# M405X.net
KiCad netlist of a schematic drawn in EAGLE
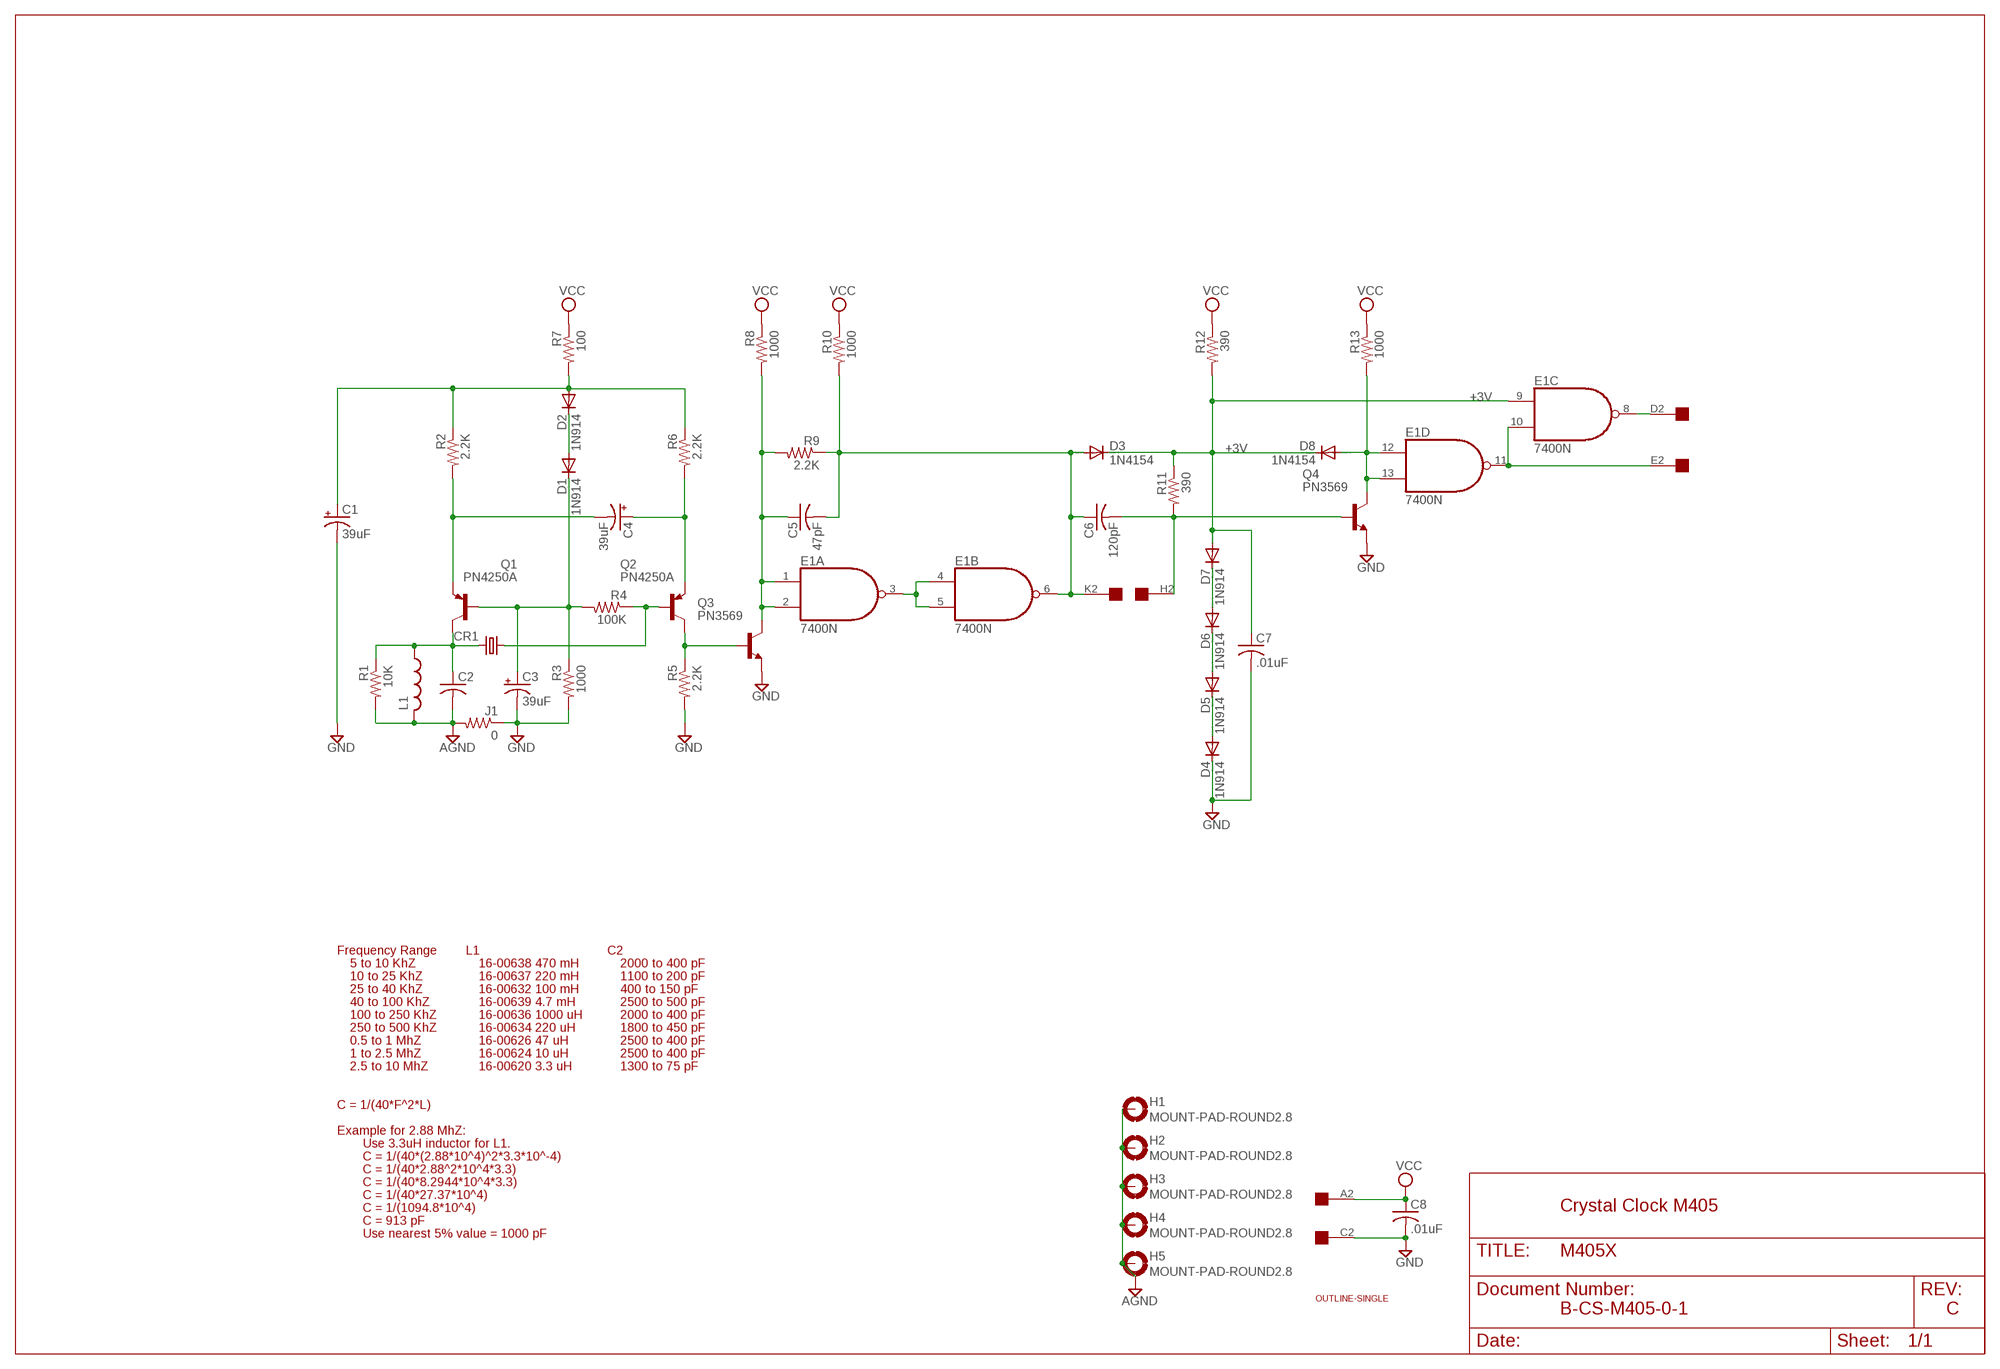
[diagram p0: schematic, sheet 1]

(export (version "E")
  (design (tool "Eeschema 10.0.6"))
  (components
    (comp (ref "C1")
      (value "39uF")
      (footprint "eagle-import:E15-5")
      (libsource (lib "eagle-import") (part "CPOL-USE15-5AXIAL"))
    )
    (comp (ref "C2")
      (value "C-US150-054X183")
      (footprint "eagle-import:C150-054X183")
      (libsource (lib "eagle-import") (part "C-US150-054X183"))
    )
    (comp (ref "C3")
      (value "39uF")
      (footprint "eagle-import:E15-5")
      (libsource (lib "eagle-import") (part "CPOL-USE15-5AXIAL"))
    )
    (comp (ref "C4")
      (value "39uF")
      (footprint "eagle-import:E15-5")
      (libsource (lib "eagle-import") (part "CPOL-USE15-5AXIAL"))
    )
    (comp (ref "C5")
      (value "47pF")
      (footprint "eagle-import:C050-025X075")
      (libsource (lib "eagle-import") (part "C-US050-025X075"))
    )
    (comp (ref "C6")
      (value "120pF")
      (footprint "eagle-import:C050-025X075")
      (libsource (lib "eagle-import") (part "C-US050-025X075"))
    )
    (comp (ref "C7")
      (value ".01uF")
      (footprint "eagle-import:C050-025X075")
      (libsource (lib "eagle-import") (part "C-US050-025X075"))
    )
    (comp (ref "C8")
      (value ".01uF")
      (footprint "eagle-import:C050-025X075")
      (libsource (lib "eagle-import") (part "C-US050-025X075"))
    )
    (comp (ref "CR1")
      (value "CRYSTALHC13U-H")
      (footprint "eagle-import:HC13U-H")
      (libsource (lib "eagle-import") (part "CRYSTALHC13U-H"))
    )
    (comp (ref "D1")
      (value "1N914")
      (footprint "eagle-import:DO35-10")
      (libsource (lib "eagle-import") (part "1N4148DO35-10"))
    )
    (comp (ref "D2")
      (value "1N914")
      (footprint "eagle-import:DO35-10")
      (libsource (lib "eagle-import") (part "1N4148DO35-10"))
    )
    (comp (ref "D3")
      (value "1N4154")
      (footprint "eagle-import:DO35-10")
      (libsource (lib "eagle-import") (part "1N4148DO35-10"))
    )
    (comp (ref "D4")
      (value "1N914")
      (footprint "eagle-import:DO35-10")
      (libsource (lib "eagle-import") (part "1N4148DO35-10"))
    )
    (comp (ref "D5")
      (value "1N914")
      (footprint "eagle-import:DO35-10")
      (libsource (lib "eagle-import") (part "1N4148DO35-10"))
    )
    (comp (ref "D6")
      (value "1N914")
      (footprint "eagle-import:DO35-10")
      (libsource (lib "eagle-import") (part "1N4148DO35-10"))
    )
    (comp (ref "D7")
      (value "1N914")
      (footprint "eagle-import:DO35-10")
      (libsource (lib "eagle-import") (part "1N4148DO35-10"))
    )
    (comp (ref "D8")
      (value "1N4154")
      (footprint "eagle-import:DO35-10")
      (libsource (lib "eagle-import") (part "1N4148DO35-10"))
    )
    (comp (ref "E1")
      (value "7400N")
      (footprint "eagle-import:DIL14")
      (libsource (lib "eagle-import") (part "7400N"))
    )
    (comp (ref "H1")
      (value "MOUNT-PAD-ROUND2.8")
      (footprint "eagle-import:2,8-PAD")
      (libsource (lib "eagle-import") (part "MOUNT-PAD-ROUND2.8"))
    )
    (comp (ref "H2")
      (value "MOUNT-PAD-ROUND2.8")
      (footprint "eagle-import:2,8-PAD")
      (libsource (lib "eagle-import") (part "MOUNT-PAD-ROUND2.8"))
    )
    (comp (ref "H3")
      (value "MOUNT-PAD-ROUND2.8")
      (footprint "eagle-import:2,8-PAD")
      (libsource (lib "eagle-import") (part "MOUNT-PAD-ROUND2.8"))
    )
    (comp (ref "H4")
      (value "MOUNT-PAD-ROUND2.8")
      (footprint "eagle-import:2,8-PAD")
      (libsource (lib "eagle-import") (part "MOUNT-PAD-ROUND2.8"))
    )
    (comp (ref "H5")
      (value "MOUNT-PAD-ROUND2.8")
      (footprint "eagle-import:2,8-PAD")
      (libsource (lib "eagle-import") (part "MOUNT-PAD-ROUND2.8"))
    )
    (comp (ref "J1")
      (value "0")
      (footprint "eagle-import:0207_10")
      (libsource (lib "eagle-import") (part "R-US_0207/10"))
    )
    (comp (ref "L1")
      (value "L-US0207/12")
      (footprint "eagle-import:0207_12")
      (libsource (lib "eagle-import") (part "L-US0207/12"))
    )
    (comp (ref "Q1")
      (value "PN4250A")
      (footprint "eagle-import:TO39")
      (libsource (lib "eagle-import") (part "-PNP-TO39-EBC2N3637"))
    )
    (comp (ref "Q2")
      (value "PN4250A")
      (footprint "eagle-import:TO39")
      (libsource (lib "eagle-import") (part "-PNP-TO39-EBC2N3637"))
    )
    (comp (ref "Q3")
      (value "PN3569")
      (footprint "eagle-import:TO39")
      (libsource (lib "eagle-import") (part "-NPN-TO39-EBC2N3019"))
    )
    (comp (ref "Q4")
      (value "PN3569")
      (footprint "eagle-import:TO39")
      (libsource (lib "eagle-import") (part "-NPN-TO39-EBC2N3019"))
    )
    (comp (ref "R1")
      (value "10K")
      (footprint "eagle-import:0207_10")
      (libsource (lib "eagle-import") (part "R-US_0207/10"))
    )
    (comp (ref "R2")
      (value "2.2K")
      (footprint "eagle-import:0207_10")
      (libsource (lib "eagle-import") (part "R-US_0207/10"))
    )
    (comp (ref "R3")
      (value "1000")
      (footprint "eagle-import:0207_10")
      (libsource (lib "eagle-import") (part "R-US_0207/10"))
    )
    (comp (ref "R4")
      (value "100K")
      (footprint "eagle-import:0207_10")
      (libsource (lib "eagle-import") (part "R-US_0207/10"))
    )
    (comp (ref "R5")
      (value "2.2K")
      (footprint "eagle-import:0207_10")
      (libsource (lib "eagle-import") (part "R-US_0207/10"))
    )
    (comp (ref "R6")
      (value "2.2K")
      (footprint "eagle-import:0207_10")
      (libsource (lib "eagle-import") (part "R-US_0207/10"))
    )
    (comp (ref "R7")
      (value "100")
      (footprint "eagle-import:0207_10")
      (libsource (lib "eagle-import") (part "R-US_0207/10"))
    )
    (comp (ref "R8")
      (value "1000")
      (footprint "eagle-import:0207_10")
      (libsource (lib "eagle-import") (part "R-US_0207/10"))
    )
    (comp (ref "R9")
      (value "2.2K")
      (footprint "eagle-import:0207_10")
      (libsource (lib "eagle-import") (part "R-US_0207/10"))
    )
    (comp (ref "R10")
      (value "1000")
      (footprint "eagle-import:0207_10")
      (libsource (lib "eagle-import") (part "R-US_0207/10"))
    )
    (comp (ref "R11")
      (value "390")
      (footprint "eagle-import:0207_10")
      (libsource (lib "eagle-import") (part "R-US_0207/10"))
    )
    (comp (ref "R12")
      (value "390")
      (footprint "eagle-import:0207_10")
      (libsource (lib "eagle-import") (part "R-US_0207/10"))
    )
    (comp (ref "R13")
      (value "1000")
      (footprint "eagle-import:0207_10")
      (libsource (lib "eagle-import") (part "R-US_0207/10"))
    )
    (comp (ref "U$1")
      (value "OUTLINE-SINGLE")
      (footprint "eagle-import:SINGLE")
      (libsource (lib "eagle-import") (part "OUTLINE-SINGLE"))
    )
    (comp (ref "U$2")
      (value "EDGE-1")
      (footprint "eagle-import:EDGE-CON1")
      (libsource (lib "eagle-import") (part "EDGE-1"))
    )
  )
  (nets
    (net (code "1") (name "/+3V") (class "Default")
      (node (ref "C7") (pin "1") (pinfunction "1_1") (pintype "passive"))
      (node (ref "D3") (pin "C") (pinfunction "C_C") (pintype "passive"))
      (node (ref "D7") (pin "A") (pinfunction "A_A") (pintype "passive"))
      (node (ref "D8") (pin "C") (pinfunction "C_C") (pintype "passive"))
      (node (ref "E1") (pin "9") (pinfunction "I0_9") (pintype "input"))
      (node (ref "R11") (pin "1") (pinfunction "1_1") (pintype "passive"))
      (node (ref "R12") (pin "2") (pinfunction "2_2") (pintype "passive"))
    )
    (net (code "2") (name "AGND") (class "Default")
      (node (ref "C2") (pin "2") (pinfunction "2_2") (pintype "passive"))
      (node (ref "H1") (pin "B2,8") (pinfunction "MOUNT_B2,8") (pintype "passive"))
      (node (ref "H2") (pin "B2,8") (pinfunction "MOUNT_B2,8") (pintype "passive"))
      (node (ref "H3") (pin "B2,8") (pinfunction "MOUNT_B2,8") (pintype "passive"))
      (node (ref "H4") (pin "B2,8") (pinfunction "MOUNT_B2,8") (pintype "passive"))
      (node (ref "H5") (pin "B2,8") (pinfunction "MOUNT_B2,8") (pintype "passive"))
      (node (ref "J1") (pin "2") (pinfunction "2_2") (pintype "passive"))
      (node (ref "L1") (pin "2") (pinfunction "2_2") (pintype "passive"))
      (node (ref "R1") (pin "2") (pinfunction "2_2") (pintype "passive"))
    )
    (net (code "3") (name "GND") (class "Default")
      (node (ref "C1") (pin "-") (pinfunction "-_-") (pintype "passive"))
      (node (ref "C3") (pin "-") (pinfunction "-_-") (pintype "passive"))
      (node (ref "C7") (pin "2") (pinfunction "2_2") (pintype "passive"))
      (node (ref "C8") (pin "2") (pinfunction "2_2") (pintype "passive"))
      (node (ref "D4") (pin "C") (pinfunction "C_C") (pintype "passive"))
      (node (ref "J1") (pin "1") (pinfunction "1_1") (pintype "passive"))
      (node (ref "Q3") (pin "1") (pinfunction "E_1") (pintype "passive"))
      (node (ref "Q4") (pin "1") (pinfunction "E_1") (pintype "passive"))
      (node (ref "R3") (pin "2") (pinfunction "2_2") (pintype "passive"))
      (node (ref "R5") (pin "2") (pinfunction "2_2") (pintype "passive"))
      (node (ref "U$2") (pin "C2") (pinfunction "1_C2") (pintype "bidirectional"))
    )
    (net (code "4") (name "Net-(C1-Pad+)") (class "Default")
      (node (ref "C1") (pin "+") (pinfunction "+_+") (pintype "passive"))
      (node (ref "D2") (pin "A") (pinfunction "A_A") (pintype "passive"))
      (node (ref "R2") (pin "1") (pinfunction "1_1") (pintype "passive"))
      (node (ref "R6") (pin "1") (pinfunction "1_1") (pintype "passive"))
      (node (ref "R7") (pin "2") (pinfunction "2_2") (pintype "passive"))
    )
    (net (code "5") (name "Net-(D1-PadA)") (class "Default")
      (node (ref "D1") (pin "A") (pinfunction "A_A") (pintype "passive"))
      (node (ref "D2") (pin "C") (pinfunction "C_C") (pintype "passive"))
    )
    (net (code "6") (name "Net-(D4-PadA)") (class "Default")
      (node (ref "D4") (pin "A") (pinfunction "A_A") (pintype "passive"))
      (node (ref "D5") (pin "C") (pinfunction "C_C") (pintype "passive"))
    )
    (net (code "7") (name "Net-(D5-PadA)") (class "Default")
      (node (ref "D5") (pin "A") (pinfunction "A_A") (pintype "passive"))
      (node (ref "D6") (pin "C") (pinfunction "C_C") (pintype "passive"))
    )
    (net (code "8") (name "Net-(D6-PadA)") (class "Default")
      (node (ref "D6") (pin "A") (pinfunction "A_A") (pintype "passive"))
      (node (ref "D7") (pin "C") (pinfunction "C_C") (pintype "passive"))
    )
    (net (code "9") (name "Net-(E1A-I0)") (class "Default")
      (node (ref "C5") (pin "1") (pinfunction "1_1") (pintype "passive"))
      (node (ref "E1") (pin "1") (pinfunction "I0_1") (pintype "input"))
      (node (ref "E1") (pin "2") (pinfunction "I1_2") (pintype "input"))
      (node (ref "Q3") (pin "3") (pinfunction "C_3") (pintype "passive"))
      (node (ref "R8") (pin "2") (pinfunction "2_2") (pintype "passive"))
      (node (ref "R9") (pin "2") (pinfunction "2_2") (pintype "passive"))
    )
    (net (code "10") (name "Net-(E1A-O)") (class "Default")
      (node (ref "E1") (pin "3") (pinfunction "O_3") (pintype "output"))
      (node (ref "E1") (pin "4") (pinfunction "I0_4") (pintype "input"))
      (node (ref "E1") (pin "5") (pinfunction "I1_5") (pintype "input"))
    )
    (net (code "11") (name "Net-(E1B-O)") (class "Default")
      (node (ref "C5") (pin "2") (pinfunction "2_2") (pintype "passive"))
      (node (ref "C6") (pin "1") (pinfunction "1_1") (pintype "passive"))
      (node (ref "D3") (pin "A") (pinfunction "A_A") (pintype "passive"))
      (node (ref "E1") (pin "6") (pinfunction "O_6") (pintype "output"))
      (node (ref "R10") (pin "2") (pinfunction "2_2") (pintype "passive"))
      (node (ref "R9") (pin "1") (pinfunction "1_1") (pintype "passive"))
      (node (ref "U$2") (pin "K2") (pinfunction "1_K2") (pintype "bidirectional"))
    )
    (net (code "12") (name "Net-(E1C-I1)") (class "Default")
      (node (ref "E1") (pin "10") (pinfunction "I1_10") (pintype "input"))
      (node (ref "E1") (pin "11") (pinfunction "O_11") (pintype "output"))
      (node (ref "U$2") (pin "E2") (pinfunction "1_E2") (pintype "bidirectional"))
    )
    (net (code "13") (name "Net-(E1C-O)") (class "Default")
      (node (ref "E1") (pin "8") (pinfunction "O_8") (pintype "output"))
      (node (ref "U$2") (pin "D2") (pinfunction "1_D2") (pintype "bidirectional"))
    )
    (net (code "14") (name "Net-(E1D-I0)") (class "Default")
      (node (ref "D8") (pin "A") (pinfunction "A_A") (pintype "passive"))
      (node (ref "E1") (pin "12") (pinfunction "I0_12") (pintype "input"))
      (node (ref "E1") (pin "13") (pinfunction "I1_13") (pintype "input"))
      (node (ref "Q4") (pin "3") (pinfunction "C_3") (pintype "passive"))
      (node (ref "R13") (pin "2") (pinfunction "2_2") (pintype "passive"))
    )
    (net (code "15") (name "Net-(Q1-B)") (class "Default")
      (node (ref "C3") (pin "+") (pinfunction "+_+") (pintype "passive"))
      (node (ref "D1") (pin "C") (pinfunction "C_C") (pintype "passive"))
      (node (ref "Q1") (pin "2") (pinfunction "B_2") (pintype "passive"))
      (node (ref "R3") (pin "1") (pinfunction "1_1") (pintype "passive"))
      (node (ref "R4") (pin "2") (pinfunction "2_2") (pintype "passive"))
    )
    (net (code "16") (name "Net-(Q1-C)") (class "Default")
      (node (ref "C2") (pin "1") (pinfunction "1_1") (pintype "passive"))
      (node (ref "CR1") (pin "2") (pinfunction "2_2") (pintype "passive"))
      (node (ref "L1") (pin "1") (pinfunction "1_1") (pintype "passive"))
      (node (ref "Q1") (pin "3") (pinfunction "C_3") (pintype "passive"))
      (node (ref "R1") (pin "1") (pinfunction "1_1") (pintype "passive"))
    )
    (net (code "17") (name "Net-(Q1-E)") (class "Default")
      (node (ref "C4") (pin "-") (pinfunction "-_-") (pintype "passive"))
      (node (ref "Q1") (pin "1") (pinfunction "E_1") (pintype "passive"))
      (node (ref "R2") (pin "2") (pinfunction "2_2") (pintype "passive"))
    )
    (net (code "18") (name "Net-(Q2-B)") (class "Default")
      (node (ref "CR1") (pin "1") (pinfunction "1_1") (pintype "passive"))
      (node (ref "Q2") (pin "2") (pinfunction "B_2") (pintype "passive"))
      (node (ref "R4") (pin "1") (pinfunction "1_1") (pintype "passive"))
    )
    (net (code "19") (name "Net-(Q2-C)") (class "Default")
      (node (ref "Q2") (pin "3") (pinfunction "C_3") (pintype "passive"))
      (node (ref "Q3") (pin "2") (pinfunction "B_2") (pintype "passive"))
      (node (ref "R5") (pin "1") (pinfunction "1_1") (pintype "passive"))
    )
    (net (code "20") (name "Net-(Q2-E)") (class "Default")
      (node (ref "C4") (pin "+") (pinfunction "+_+") (pintype "passive"))
      (node (ref "Q2") (pin "1") (pinfunction "E_1") (pintype "passive"))
      (node (ref "R6") (pin "2") (pinfunction "2_2") (pintype "passive"))
    )
    (net (code "21") (name "Net-(Q4-B)") (class "Default")
      (node (ref "C6") (pin "2") (pinfunction "2_2") (pintype "passive"))
      (node (ref "Q4") (pin "2") (pinfunction "B_2") (pintype "passive"))
      (node (ref "R11") (pin "2") (pinfunction "2_2") (pintype "passive"))
      (node (ref "U$2") (pin "H2") (pinfunction "1_H2") (pintype "bidirectional"))
    )
    (net (code "22") (name "VCC") (class "Default")
      (node (ref "C8") (pin "1") (pinfunction "1_1") (pintype "passive"))
      (node (ref "R10") (pin "1") (pinfunction "1_1") (pintype "passive"))
      (node (ref "R12") (pin "1") (pinfunction "1_1") (pintype "passive"))
      (node (ref "R13") (pin "1") (pinfunction "1_1") (pintype "passive"))
      (node (ref "R7") (pin "1") (pinfunction "1_1") (pintype "passive"))
      (node (ref "R8") (pin "1") (pinfunction "1_1") (pintype "passive"))
      (node (ref "U$2") (pin "A2") (pinfunction "1_A2") (pintype "bidirectional"))
    )
  )
)
